# Power.net
KiCad netlist of a schematic drawn in Altium Designer
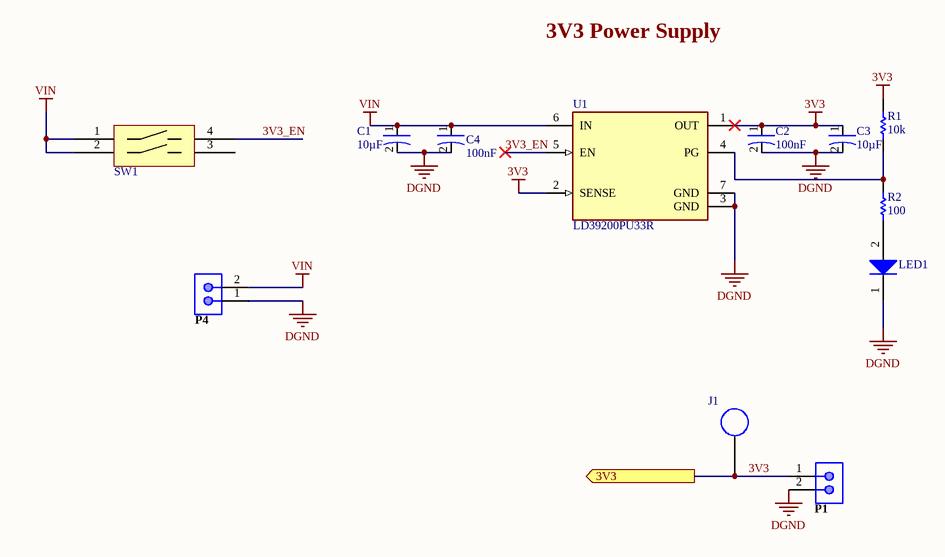
[diagram p0: Power.SchDoc]

(export (version "E")
  (design (tool "Eeschema 10.0.6"))
  (components
    (comp (ref "C1")
      (value "10µF")
      (footprint "0402-M")
      (description "CAP-10uF-CER-0402-6.3V-X5R-20%")
      (fields
        (field (name "MANUFACTURER") "Generic")
        (field (name "Comment") "CAP 10uF CER 0402 6.3V X5R 20%")
      )
      (libsource (lib "University of Malta - MEMENTO") (part "Symbol"))
    )
    (comp (ref "C2")
      (value "100nF")
      (footprint "0402-M")
      (description "CAP-0.1uF-CER-0402-16V-X5R-10%")
      (fields
        (field (name "MANUFACTURER") "Generic")
        (field (name "Comment") "CAP 0.1uF CER 0402 16V X5R 10%")
      )
      (libsource (lib "University of Malta - MEMENTO") (part "Symbol"))
    )
    (comp (ref "C3")
      (value "10µF")
      (footprint "0402-M")
      (description "CAP-10uF-CER-0402-6.3V-X5R-20%")
      (fields
        (field (name "MANUFACTURER") "Generic")
        (field (name "Comment") "CAP 10uF CER 0402 6.3V X5R 20%")
      )
      (libsource (lib "University of Malta - MEMENTO") (part "Symbol"))
    )
    (comp (ref "C4")
      (value "100nF")
      (footprint "0805-M")
      (description "CAP-0.1uF-CER-0805-50V-X7R-10%")
      (fields
        (field (name "MANUFACTURER") "Generic")
        (field (name "Comment") "CAP 0.1uF CER 0805 50V X7R 10%")
      )
      (libsource (lib "University of Malta - MEMENTO") (part "Symbol"))
    )
    (comp (ref "J1")
      (value "151-203-RC")
      (footprint "151-203-RC-Footprint-1")
      (description "PCB-Probe-Ring")
      (libsource (lib "University of Malta - MEMENTO") (part "PCB Probe Ring"))
    )
    (comp (ref "LED1")
      (value "LED 0603 Green 20mA 1.8V")
      (footprint "0603 Generic")
      (description "LED-0603-Green-20mA-1.8V-STOCK")
      (fields (field (name "MANUFACTURER") "Generic"))
      (libsource (lib "") (part "Symbol_2"))
    )
    (comp (ref "P1")
      (value "GENERIC 2PIN HEADER MALE")
      (footprint "GENERIC 2PIN HEADER 0")
      (description "CONN MAL TH 2 0Deg HEADER")
      (fields (field (name "MANUFACTURER") "Generic"))
      (libsource (lib "University of Malta - MEMENTO") (part "GENERIC 2PIN HEADER MALE"))
    )
    (comp (ref "P4")
      (value "GENERIC 2PIN HEADER MALE")
      (footprint "GENERIC 2PIN HEADER 0")
      (description "CONN MAL TH 2 0Deg HEADER")
      (fields (field (name "MANUFACTURER") "Generic"))
      (libsource (lib "") (part "GENERIC 2PIN HEADER MALE_1"))
    )
    (comp (ref "R1")
      (value "10k")
      (footprint "0402-M")
      (description "RES-10k-0402-63mW-5%")
      (fields (field (name "MANUFACTURER") "Generic") (field (name "Comment") "RES 10k 0402 63mW 5%"))
      (libsource (lib "") (part "Symbol_1"))
    )
    (comp (ref "R2")
      (value "100")
      (footprint "0805-L")
      (description "RES-100-0805-125mW-1%")
      (fields (field (name "MANUFACTURER") "Generic") (field (name "Comment") "RES 100 0805 125mW 1%"))
      (libsource (lib "") (part "Symbol_1"))
    )
    (comp (ref "SW1")
      (value "210-2MS")
      (footprint "210-2MS-Footprint-1")
      (description "SWITCH DIP SPST 2 100mA 50V")
      (libsource (lib "University of Malta - MEMENTO") (part "210-2MS"))
    )
    (comp (ref "U1")
      (value "LD39200PU33R")
      (footprint "FP-DFN6-7946637-MFG")
      (description "STMICROELECTRONICS - LD39200PU33R - LDO, FIXED, 3.3V, 2A, -40 TO 125DEG C")
      (fields (field (name "MANUFACTURER") "STMicroelectronics"))
      (libsource (lib "University of Malta - MEMENTO") (part "f0cfe00d12cb984572f50007c934a2d"))
    )
  )
  (nets
    (net (code "1") (name "/3V3_EN") (class "Default")
      (node (ref "SW1") (pin "4") (pinfunction "4_4") (pintype "passive"))
      (node (ref "U1") (pin "5") (pinfunction "EN_5") (pintype "input"))
    )
    (net (code "2") (name "3V3") (class "Default")
      (node (ref "C2") (pin "1") (pinfunction "Anode_1") (pintype "passive"))
      (node (ref "C3") (pin "1") (pinfunction "Anode_1") (pintype "passive"))
      (node (ref "J1") (pin "1") (pinfunction "1_1") (pintype "passive"))
      (node (ref "P1") (pin "1") (pinfunction "1_1") (pintype "passive"))
      (node (ref "R1") (pin "2") (pinfunction "2_2") (pintype "passive"))
      (node (ref "U1") (pin "1") (pinfunction "OUT_1") (pintype "power_in"))
      (node (ref "U1") (pin "2") (pinfunction "SENSE_2") (pintype "input"))
    )
    (net (code "3") (name "DGND") (class "Default")
      (node (ref "C1") (pin "2") (pinfunction "Cathode_2") (pintype "passive"))
      (node (ref "C2") (pin "2") (pinfunction "Cathode_2") (pintype "passive"))
      (node (ref "C3") (pin "2") (pinfunction "Cathode_2") (pintype "passive"))
      (node (ref "C4") (pin "2") (pinfunction "Cathode_2") (pintype "passive"))
      (node (ref "LED1") (pin "1") (pinfunction "1_1") (pintype "passive"))
      (node (ref "P1") (pin "2") (pinfunction "2_2") (pintype "passive"))
      (node (ref "P4") (pin "1") (pinfunction "1_1") (pintype "passive"))
      (node (ref "U1") (pin "3") (pinfunction "GND_3") (pintype "power_in"))
      (node (ref "U1") (pin "7") (pinfunction "GND_7") (pintype "power_in"))
    )
    (net (code "4") (name "Net-(LED1-Pad2)") (class "Default")
      (node (ref "LED1") (pin "2") (pinfunction "2_2") (pintype "passive"))
      (node (ref "R2") (pin "1") (pinfunction "1_1") (pintype "passive"))
    )
    (net (code "5") (name "Net-(U1-PG)") (class "Default")
      (node (ref "R1") (pin "1") (pinfunction "1_1") (pintype "passive"))
      (node (ref "R2") (pin "2") (pinfunction "2_2") (pintype "passive"))
      (node (ref "U1") (pin "4") (pinfunction "PG_4") (pintype "open_collector"))
    )
    (net (code "6") (name "VIN") (class "Default")
      (node (ref "C1") (pin "1") (pinfunction "Anode_1") (pintype "passive"))
      (node (ref "C4") (pin "1") (pinfunction "Anode_1") (pintype "passive"))
      (node (ref "P4") (pin "2") (pinfunction "2_2") (pintype "passive"))
      (node (ref "SW1") (pin "1") (pinfunction "1_1") (pintype "passive"))
      (node (ref "SW1") (pin "2") (pinfunction "2_2") (pintype "passive"))
      (node (ref "U1") (pin "6") (pinfunction "IN_6") (pintype "power_in"))
    )
    (net (code "7") (name "unconnected-(SW1-4-Pad3)") (class "Default")
      (node (ref "SW1") (pin "3") (pinfunction "4_3") (pintype "passive"))
    )
  )
)
